# astable_mul.net
KiCad netlist of a schematic drawn in EAGLE
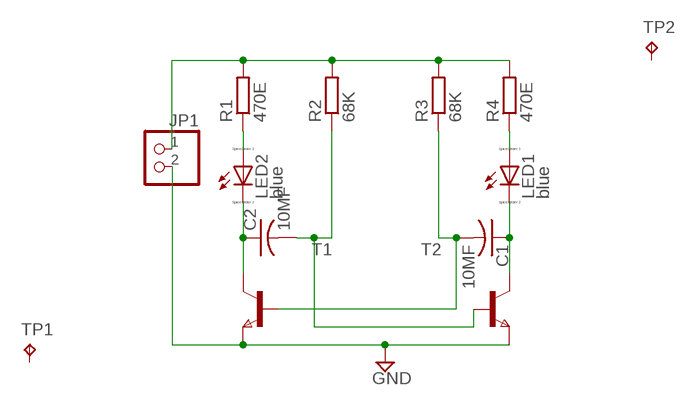
[diagram p0: schematic, sheet 1]

(export (version "E")
  (design (tool "Eeschema 10.0.6"))
  (components
    (comp (ref "C1")
      (value "10MF")
      (footprint "eagle-import:C050-025X075")
      (libsource (lib "eagle-import") (part "C-US050-025X075"))
    )
    (comp (ref "C2")
      (value "10MF")
      (footprint "eagle-import:C050-025X075")
      (libsource (lib "eagle-import") (part "C-US050-025X075"))
    )
    (comp (ref "JP1")
      (value "PINHD-1X2")
      (footprint "eagle-import:1X02")
      (libsource (lib "eagle-import") (part "PINHD-1X2"))
    )
    (comp (ref "LED1")
      (value "blue")
      (footprint "eagle-import:LED_1206")
      (libsource (lib "eagle-import") (part "LED_E"))
    )
    (comp (ref "LED2")
      (value "blue")
      (footprint "eagle-import:LED_1206")
      (libsource (lib "eagle-import") (part "LED_E"))
    )
    (comp (ref "R1")
      (value "470E")
      (footprint "eagle-import:R0805")
      (libsource (lib "eagle-import") (part "R-EU_R0805"))
    )
    (comp (ref "R2")
      (value "68K")
      (footprint "eagle-import:R0805")
      (libsource (lib "eagle-import") (part "R-EU_R0805"))
    )
    (comp (ref "R3")
      (value "68K")
      (footprint "eagle-import:R0805")
      (libsource (lib "eagle-import") (part "R-EU_R0805"))
    )
    (comp (ref "R4")
      (value "470E")
      (footprint "eagle-import:R0805")
      (libsource (lib "eagle-import") (part "R-EU_R0805"))
    )
    (comp (ref "T1")
      (value "NPNSOT23")
      (footprint "eagle-import:SOT-23")
      (fields (field (name "MPN") "DSS20201L-7"))
      (libsource (lib "eagle-import") (part "NPNSOT23"))
    )
    (comp (ref "T2")
      (value "NPNSOT23")
      (footprint "eagle-import:SOT-23")
      (fields (field (name "MPN") "DSS20201L-7"))
      (libsource (lib "eagle-import") (part "NPNSOT23"))
    )
    (comp (ref "TP1")
      (value "TPB1,27")
      (footprint "eagle-import:B1,27")
      (libsource (lib "eagle-import") (part "TPB1,27"))
    )
    (comp (ref "TP2")
      (value "TPB1,27")
      (footprint "eagle-import:B1,27")
      (libsource (lib "eagle-import") (part "TPB1,27"))
    )
  )
  (nets
    (net (code "1") (name "GND") (class "Default")
      (node (ref "JP1") (pin "2") (pinfunction "2_2") (pintype "passive"))
      (node (ref "T1") (pin "2") (pinfunction "E_2") (pintype "passive"))
      (node (ref "T2") (pin "2") (pinfunction "E_2") (pintype "passive"))
    )
    (net (code "2") (name "Net-(JP1-Pad1)") (class "Default")
      (node (ref "JP1") (pin "1") (pinfunction "1_1") (pintype "passive"))
      (node (ref "R1") (pin "2") (pinfunction "2_2") (pintype "passive"))
      (node (ref "R2") (pin "2") (pinfunction "2_2") (pintype "passive"))
      (node (ref "R3") (pin "2") (pinfunction "2_2") (pintype "passive"))
      (node (ref "R4") (pin "2") (pinfunction "2_2") (pintype "passive"))
    )
    (net (code "3") (name "Net-(LED1-PadA)") (class "Default")
      (node (ref "LED1") (pin "A") (pinfunction "A_A") (pintype "passive"))
      (node (ref "R4") (pin "1") (pinfunction "1_1") (pintype "passive"))
    )
    (net (code "4") (name "Net-(LED2-PadA)") (class "Default")
      (node (ref "LED2") (pin "A") (pinfunction "A_A") (pintype "passive"))
      (node (ref "R1") (pin "1") (pinfunction "1_1") (pintype "passive"))
    )
    (net (code "5") (name "Net-(T1-B)") (class "Default")
      (node (ref "C1") (pin "2") (pinfunction "2_2") (pintype "passive"))
      (node (ref "R3") (pin "1") (pinfunction "1_1") (pintype "passive"))
      (node (ref "T1") (pin "3") (pinfunction "B_3") (pintype "passive"))
    )
    (net (code "6") (name "Net-(T1-C)") (class "Default")
      (node (ref "C2") (pin "1") (pinfunction "1_1") (pintype "passive"))
      (node (ref "LED2") (pin "C") (pinfunction "C_C") (pintype "passive"))
      (node (ref "T1") (pin "1") (pinfunction "C_1") (pintype "passive"))
    )
    (net (code "7") (name "Net-(T2-B)") (class "Default")
      (node (ref "C2") (pin "2") (pinfunction "2_2") (pintype "passive"))
      (node (ref "R2") (pin "1") (pinfunction "1_1") (pintype "passive"))
      (node (ref "T2") (pin "3") (pinfunction "B_3") (pintype "passive"))
    )
    (net (code "8") (name "Net-(T2-C)") (class "Default")
      (node (ref "C1") (pin "1") (pinfunction "1_1") (pintype "passive"))
      (node (ref "LED1") (pin "C") (pinfunction "C_C") (pintype "passive"))
      (node (ref "T2") (pin "1") (pinfunction "C_1") (pintype "passive"))
    )
    (net (code "9") (name "unconnected-(TP1-PadTP)") (class "Default")
      (node (ref "TP1") (pin "TP") (pinfunction "TP_TP") (pintype "input"))
    )
    (net (code "10") (name "unconnected-(TP2-PadTP)") (class "Default")
      (node (ref "TP2") (pin "TP") (pinfunction "TP_TP") (pintype "input"))
    )
  )
)
